# RadioInterfaceMain.net
KiCad netlist of a schematic drawn in EAGLE
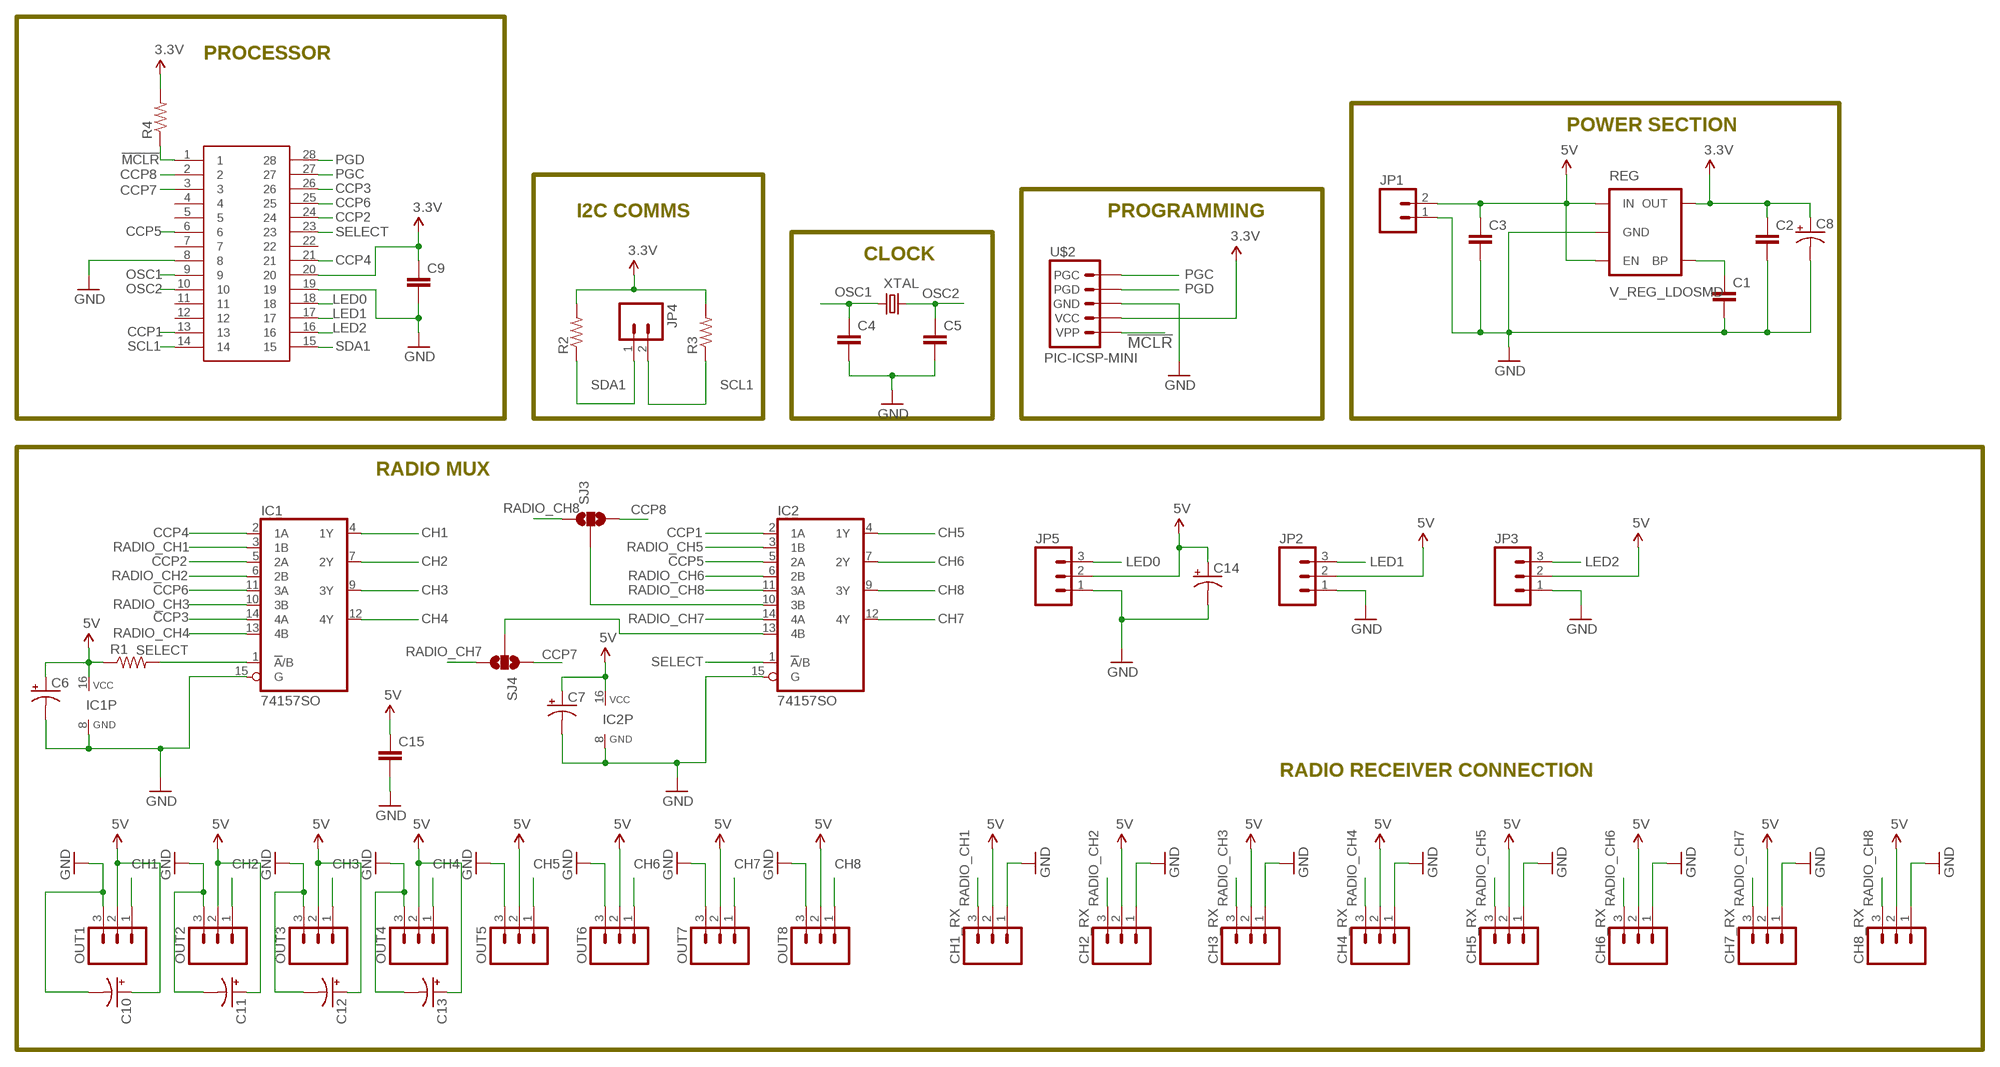
[diagram p0: schematic, sheet 1]

(export (version "E")
  (design (tool "Eeschema 10.0.6"))
  (components
    (comp (ref "C1")
      (value "CAP0603-CAP")
      (footprint "eagle-import:0603-CAP")
      (libsource (lib "eagle-import") (part "CAP0603-CAP"))
    )
    (comp (ref "C2")
      (value "CAP1210")
      (footprint "eagle-import:1210")
      (libsource (lib "eagle-import") (part "CAP1210"))
    )
    (comp (ref "C3")
      (value "CAP1210")
      (footprint "eagle-import:1210")
      (libsource (lib "eagle-import") (part "CAP1210"))
    )
    (comp (ref "C4")
      (value "CAP0603-CAP")
      (footprint "eagle-import:0603-CAP")
      (libsource (lib "eagle-import") (part "CAP0603-CAP"))
    )
    (comp (ref "C5")
      (value "CAP0603-CAP")
      (footprint "eagle-import:0603-CAP")
      (libsource (lib "eagle-import") (part "CAP0603-CAP"))
    )
    (comp (ref "C6")
      (value "CAP_POL1206")
      (footprint "eagle-import:EIA3216")
      (libsource (lib "eagle-import") (part "CAP_POL1206"))
    )
    (comp (ref "C7")
      (value "CAP_POL1206")
      (footprint "eagle-import:EIA3216")
      (libsource (lib "eagle-import") (part "CAP_POL1206"))
    )
    (comp (ref "C8")
      (value "CAP_POL1206")
      (footprint "eagle-import:EIA3216")
      (libsource (lib "eagle-import") (part "CAP_POL1206"))
    )
    (comp (ref "C9")
      (value "CAP0603-CAP")
      (footprint "eagle-import:0603-CAP")
      (libsource (lib "eagle-import") (part "CAP0603-CAP"))
    )
    (comp (ref "C10")
      (value "CAP_POL1206")
      (footprint "eagle-import:EIA3216")
      (libsource (lib "eagle-import") (part "CAP_POL1206"))
    )
    (comp (ref "C11")
      (value "CAP_POL1206")
      (footprint "eagle-import:EIA3216")
      (libsource (lib "eagle-import") (part "CAP_POL1206"))
    )
    (comp (ref "C12")
      (value "CAP_POL1206")
      (footprint "eagle-import:EIA3216")
      (libsource (lib "eagle-import") (part "CAP_POL1206"))
    )
    (comp (ref "C13")
      (value "CAP_POL1206")
      (footprint "eagle-import:EIA3216")
      (libsource (lib "eagle-import") (part "CAP_POL1206"))
    )
    (comp (ref "C14")
      (value "CAP_POL1206")
      (footprint "eagle-import:EIA3216")
      (libsource (lib "eagle-import") (part "CAP_POL1206"))
    )
    (comp (ref "C15")
      (value "CAP0603-CAP")
      (footprint "eagle-import:0603-CAP")
      (libsource (lib "eagle-import") (part "CAP0603-CAP"))
    )
    (comp (ref "CH1_RX")
      (value "M03PTH")
      (footprint "eagle-import:1X03")
      (libsource (lib "eagle-import") (part "M03PTH"))
    )
    (comp (ref "CH2_RX")
      (value "M03PTH")
      (footprint "eagle-import:1X03")
      (libsource (lib "eagle-import") (part "M03PTH"))
    )
    (comp (ref "CH3_RX")
      (value "M03PTH")
      (footprint "eagle-import:1X03")
      (libsource (lib "eagle-import") (part "M03PTH"))
    )
    (comp (ref "CH4_RX")
      (value "M03PTH")
      (footprint "eagle-import:1X03")
      (libsource (lib "eagle-import") (part "M03PTH"))
    )
    (comp (ref "CH5_RX")
      (value "M03PTH")
      (footprint "eagle-import:1X03")
      (libsource (lib "eagle-import") (part "M03PTH"))
    )
    (comp (ref "CH6_RX")
      (value "M03PTH")
      (footprint "eagle-import:1X03")
      (libsource (lib "eagle-import") (part "M03PTH"))
    )
    (comp (ref "CH7_RX")
      (value "M03PTH")
      (footprint "eagle-import:1X03")
      (libsource (lib "eagle-import") (part "M03PTH"))
    )
    (comp (ref "CH8_RX")
      (value "M03PTH")
      (footprint "eagle-import:1X03")
      (libsource (lib "eagle-import") (part "M03PTH"))
    )
    (comp (ref "IC1")
      (value "74157SO")
      (footprint "eagle-import:SO016")
      (libsource (lib "eagle-import") (part "74157SO"))
    )
    (comp (ref "IC2")
      (value "74157SO")
      (footprint "eagle-import:SO016")
      (libsource (lib "eagle-import") (part "74157SO"))
    )
    (comp (ref "JP1")
      (value "M02-JST-2MM-SMT")
      (footprint "eagle-import:JST-2-SMD")
      (libsource (lib "eagle-import") (part "M02-JST-2MM-SMT"))
    )
    (comp (ref "JP2")
      (value "M03JST-PTH")
      (footprint "eagle-import:JST-3-PTH")
      (libsource (lib "eagle-import") (part "M03JST-PTH"))
    )
    (comp (ref "JP3")
      (value "M03JST-PTH")
      (footprint "eagle-import:JST-3-PTH")
      (libsource (lib "eagle-import") (part "M03JST-PTH"))
    )
    (comp (ref "JP4")
      (value "M02-JST-2MM-SMT")
      (footprint "eagle-import:JST-2-SMD")
      (libsource (lib "eagle-import") (part "M02-JST-2MM-SMT"))
    )
    (comp (ref "JP5")
      (value "M03JST-PTH")
      (footprint "eagle-import:JST-3-PTH")
      (libsource (lib "eagle-import") (part "M03JST-PTH"))
    )
    (comp (ref "OUT1")
      (value "M03PTH")
      (footprint "eagle-import:1X03")
      (libsource (lib "eagle-import") (part "M03PTH"))
    )
    (comp (ref "OUT2")
      (value "M03PTH")
      (footprint "eagle-import:1X03")
      (libsource (lib "eagle-import") (part "M03PTH"))
    )
    (comp (ref "OUT3")
      (value "M03PTH")
      (footprint "eagle-import:1X03")
      (libsource (lib "eagle-import") (part "M03PTH"))
    )
    (comp (ref "OUT4")
      (value "M03PTH")
      (footprint "eagle-import:1X03")
      (libsource (lib "eagle-import") (part "M03PTH"))
    )
    (comp (ref "OUT5")
      (value "M03PTH")
      (footprint "eagle-import:1X03")
      (libsource (lib "eagle-import") (part "M03PTH"))
    )
    (comp (ref "OUT6")
      (value "M03PTH")
      (footprint "eagle-import:1X03")
      (libsource (lib "eagle-import") (part "M03PTH"))
    )
    (comp (ref "OUT7")
      (value "M03PTH")
      (footprint "eagle-import:1X03")
      (libsource (lib "eagle-import") (part "M03PTH"))
    )
    (comp (ref "OUT8")
      (value "M03PTH")
      (footprint "eagle-import:1X03")
      (libsource (lib "eagle-import") (part "M03PTH"))
    )
    (comp (ref "PIC18F26K22")
      (value "SSOP28")
      (footprint "eagle-import:SSOP28DB")
      (libsource (lib "eagle-import") (part "SSOP28"))
    )
    (comp (ref "R1")
      (value "RESISTOR0603-RES")
      (footprint "eagle-import:0603-RES")
      (libsource (lib "eagle-import") (part "RESISTOR0603-RES"))
    )
    (comp (ref "R2")
      (value "RESISTOR0603-RES")
      (footprint "eagle-import:0603-RES")
      (libsource (lib "eagle-import") (part "RESISTOR0603-RES"))
    )
    (comp (ref "R3")
      (value "RESISTOR0603-RES")
      (footprint "eagle-import:0603-RES")
      (libsource (lib "eagle-import") (part "RESISTOR0603-RES"))
    )
    (comp (ref "R4")
      (value "RESISTOR0603-RES")
      (footprint "eagle-import:0603-RES")
      (libsource (lib "eagle-import") (part "RESISTOR0603-RES"))
    )
    (comp (ref "REG")
      (value "V_REG_LDOSMD")
      (footprint "eagle-import:SOT23-5")
      (libsource (lib "eagle-import") (part "V_REG_LDOSMD"))
    )
    (comp (ref "SJ3")
      (value "SOLDERJUMPER_2WAY-OLDS")
      (footprint "eagle-import:SJ_3")
      (libsource (lib "eagle-import") (part "SOLDERJUMPER_2WAY-OLDS"))
    )
    (comp (ref "SJ4")
      (value "SOLDERJUMPER_2WAY-OLDS")
      (footprint "eagle-import:SJ_3")
      (libsource (lib "eagle-import") (part "SOLDERJUMPER_2WAY-OLDS"))
    )
    (comp (ref "U$2")
      (value "PIC-ICSP-MINI")
      (footprint "eagle-import:PIC-ICSP-MINI")
      (libsource (lib "eagle-import") (part "PIC-ICSP-MINI"))
    )
    (comp (ref "XTAL")
      (value "CRYSTAL5X3")
      (footprint "eagle-import:CRYSTAL-SMD-5X3")
      (libsource (lib "eagle-import") (part "CRYSTAL5X3"))
    )
  )
  (nets
    (net (code "1") (name "/CCP1") (class "Default")
      (node (ref "IC2") (pin "2") (pinfunction "1A_2") (pintype "input"))
      (node (ref "PIC18F26K22") (pin "13") (pinfunction "13_13") (pintype "bidirectional"))
    )
    (net (code "2") (name "/CCP2") (class "Default")
      (node (ref "IC1") (pin "5") (pinfunction "2A_5") (pintype "input"))
      (node (ref "PIC18F26K22") (pin "24") (pinfunction "24_24") (pintype "bidirectional"))
    )
    (net (code "3") (name "/CCP3") (class "Default")
      (node (ref "IC1") (pin "14") (pinfunction "4A_14") (pintype "input"))
      (node (ref "PIC18F26K22") (pin "26") (pinfunction "26_26") (pintype "bidirectional"))
    )
    (net (code "4") (name "/CCP4") (class "Default")
      (node (ref "IC1") (pin "2") (pinfunction "1A_2") (pintype "input"))
      (node (ref "PIC18F26K22") (pin "21") (pinfunction "21_21") (pintype "bidirectional"))
    )
    (net (code "5") (name "/CCP5") (class "Default")
      (node (ref "IC2") (pin "5") (pinfunction "2A_5") (pintype "input"))
      (node (ref "PIC18F26K22") (pin "6") (pinfunction "6_6") (pintype "bidirectional"))
    )
    (net (code "6") (name "/CCP6") (class "Default")
      (node (ref "IC1") (pin "11") (pinfunction "3A_11") (pintype "input"))
      (node (ref "PIC18F26K22") (pin "25") (pinfunction "25_25") (pintype "bidirectional"))
    )
    (net (code "7") (name "/CCP7") (class "Default")
      (node (ref "PIC18F26K22") (pin "3") (pinfunction "3_3") (pintype "bidirectional"))
      (node (ref "SJ4") (pin "1") (pinfunction "1_1") (pintype "passive"))
    )
    (net (code "8") (name "/CCP8") (class "Default")
      (node (ref "PIC18F26K22") (pin "2") (pinfunction "2_2") (pintype "bidirectional"))
      (node (ref "SJ3") (pin "3") (pinfunction "3_3") (pintype "passive"))
    )
    (net (code "9") (name "/CH1") (class "Default")
      (node (ref "IC1") (pin "4") (pinfunction "1Y_4") (pintype "output"))
      (node (ref "OUT1") (pin "1") (pinfunction "1_1") (pintype "passive"))
    )
    (net (code "10") (name "/CH2") (class "Default")
      (node (ref "IC1") (pin "7") (pinfunction "2Y_7") (pintype "output"))
      (node (ref "OUT2") (pin "1") (pinfunction "1_1") (pintype "passive"))
    )
    (net (code "11") (name "/CH3") (class "Default")
      (node (ref "IC1") (pin "9") (pinfunction "3Y_9") (pintype "output"))
      (node (ref "OUT3") (pin "1") (pinfunction "1_1") (pintype "passive"))
    )
    (net (code "12") (name "/CH4") (class "Default")
      (node (ref "IC1") (pin "12") (pinfunction "4Y_12") (pintype "output"))
      (node (ref "OUT4") (pin "1") (pinfunction "1_1") (pintype "passive"))
    )
    (net (code "13") (name "/CH5") (class "Default")
      (node (ref "IC2") (pin "4") (pinfunction "1Y_4") (pintype "output"))
      (node (ref "OUT5") (pin "1") (pinfunction "1_1") (pintype "passive"))
    )
    (net (code "14") (name "/CH6") (class "Default")
      (node (ref "IC2") (pin "7") (pinfunction "2Y_7") (pintype "output"))
      (node (ref "OUT6") (pin "1") (pinfunction "1_1") (pintype "passive"))
    )
    (net (code "15") (name "/CH7") (class "Default")
      (node (ref "IC2") (pin "12") (pinfunction "4Y_12") (pintype "output"))
      (node (ref "OUT7") (pin "1") (pinfunction "1_1") (pintype "passive"))
    )
    (net (code "16") (name "/CH8") (class "Default")
      (node (ref "IC2") (pin "9") (pinfunction "3Y_9") (pintype "output"))
      (node (ref "OUT8") (pin "1") (pinfunction "1_1") (pintype "passive"))
    )
    (net (code "17") (name "/LED0") (class "Default")
      (node (ref "JP5") (pin "3") (pinfunction "3_3") (pintype "passive"))
      (node (ref "PIC18F26K22") (pin "18") (pinfunction "18_18") (pintype "bidirectional"))
    )
    (net (code "18") (name "/LED1") (class "Default")
      (node (ref "JP2") (pin "3") (pinfunction "3_3") (pintype "passive"))
      (node (ref "PIC18F26K22") (pin "17") (pinfunction "17_17") (pintype "bidirectional"))
    )
    (net (code "19") (name "/LED2") (class "Default")
      (node (ref "JP3") (pin "3") (pinfunction "3_3") (pintype "passive"))
      (node (ref "PIC18F26K22") (pin "16") (pinfunction "16_16") (pintype "bidirectional"))
    )
    (net (code "20") (name "/OSC1") (class "Default")
      (node (ref "C4") (pin "1") (pinfunction "1_1") (pintype "passive"))
      (node (ref "PIC18F26K22") (pin "9") (pinfunction "9_9") (pintype "bidirectional"))
      (node (ref "XTAL") (pin "1") (pinfunction "1_1") (pintype "passive"))
    )
    (net (code "21") (name "/OSC2") (class "Default")
      (node (ref "C5") (pin "1") (pinfunction "1_1") (pintype "passive"))
      (node (ref "PIC18F26K22") (pin "10") (pinfunction "10_10") (pintype "bidirectional"))
      (node (ref "XTAL") (pin "3") (pinfunction "2_3") (pintype "passive"))
    )
    (net (code "22") (name "/PGC") (class "Default")
      (node (ref "PIC18F26K22") (pin "27") (pinfunction "27_27") (pintype "bidirectional"))
      (node (ref "U$2") (pin "5") (pinfunction "PGC_5") (pintype "passive"))
    )
    (net (code "23") (name "/PGD") (class "Default")
      (node (ref "PIC18F26K22") (pin "28") (pinfunction "28_28") (pintype "bidirectional"))
      (node (ref "U$2") (pin "4") (pinfunction "PGD_4") (pintype "passive"))
    )
    (net (code "24") (name "/RADIO_CH1") (class "Default")
      (node (ref "CH1_RX") (pin "3") (pinfunction "3_3") (pintype "passive"))
      (node (ref "IC1") (pin "3") (pinfunction "1B_3") (pintype "input"))
    )
    (net (code "25") (name "/RADIO_CH2") (class "Default")
      (node (ref "CH2_RX") (pin "3") (pinfunction "3_3") (pintype "passive"))
      (node (ref "IC1") (pin "6") (pinfunction "2B_6") (pintype "input"))
    )
    (net (code "26") (name "/RADIO_CH3") (class "Default")
      (node (ref "CH3_RX") (pin "3") (pinfunction "3_3") (pintype "passive"))
      (node (ref "IC1") (pin "10") (pinfunction "3B_10") (pintype "input"))
    )
    (net (code "27") (name "/RADIO_CH4") (class "Default")
      (node (ref "CH4_RX") (pin "3") (pinfunction "3_3") (pintype "passive"))
      (node (ref "IC1") (pin "13") (pinfunction "4B_13") (pintype "input"))
    )
    (net (code "28") (name "/RADIO_CH5") (class "Default")
      (node (ref "CH5_RX") (pin "3") (pinfunction "3_3") (pintype "passive"))
      (node (ref "IC2") (pin "3") (pinfunction "1B_3") (pintype "input"))
    )
    (net (code "29") (name "/RADIO_CH6") (class "Default")
      (node (ref "CH6_RX") (pin "3") (pinfunction "3_3") (pintype "passive"))
      (node (ref "IC2") (pin "6") (pinfunction "2B_6") (pintype "input"))
    )
    (net (code "30") (name "/RADIO_CH7") (class "Default")
      (node (ref "CH7_RX") (pin "3") (pinfunction "3_3") (pintype "passive"))
      (node (ref "IC2") (pin "14") (pinfunction "4A_14") (pintype "input"))
      (node (ref "SJ4") (pin "3") (pinfunction "3_3") (pintype "passive"))
    )
    (net (code "31") (name "/RADIO_CH8") (class "Default")
      (node (ref "CH8_RX") (pin "3") (pinfunction "3_3") (pintype "passive"))
      (node (ref "IC2") (pin "11") (pinfunction "3A_11") (pintype "input"))
      (node (ref "SJ3") (pin "1") (pinfunction "1_1") (pintype "passive"))
    )
    (net (code "32") (name "/SCL1") (class "Default")
      (node (ref "JP4") (pin "2") (pinfunction "2_2") (pintype "passive"))
      (node (ref "PIC18F26K22") (pin "14") (pinfunction "14_14") (pintype "bidirectional"))
      (node (ref "R3") (pin "1") (pinfunction "1_1") (pintype "passive"))
    )
    (net (code "33") (name "/SDA1") (class "Default")
      (node (ref "JP4") (pin "1") (pinfunction "1_1") (pintype "passive"))
      (node (ref "PIC18F26K22") (pin "15") (pinfunction "15_15") (pintype "bidirectional"))
      (node (ref "R2") (pin "1") (pinfunction "1_1") (pintype "passive"))
    )
    (net (code "34") (name "/SELECT") (class "Default")
      (node (ref "IC1") (pin "1") (pinfunction "~{A}/B_1") (pintype "input"))
      (node (ref "IC2") (pin "1") (pinfunction "~{A}/B_1") (pintype "input"))
      (node (ref "PIC18F26K22") (pin "23") (pinfunction "23_23") (pintype "bidirectional"))
      (node (ref "R1") (pin "2") (pinfunction "2_2") (pintype "passive"))
    )
    (net (code "35") (name "/~{MCLR}") (class "Default")
      (node (ref "PIC18F26K22") (pin "1") (pinfunction "1_1") (pintype "bidirectional"))
      (node (ref "R4") (pin "1") (pinfunction "1_1") (pintype "passive"))
      (node (ref "U$2") (pin "1") (pinfunction "VPP_1") (pintype "passive"))
    )
    (net (code "36") (name "3.3V") (class "Default")
      (node (ref "C2") (pin "1") (pinfunction "1_1") (pintype "passive"))
      (node (ref "C8") (pin "A") (pinfunction "+_A") (pintype "passive"))
      (node (ref "C9") (pin "1") (pinfunction "1_1") (pintype "passive"))
      (node (ref "PIC18F26K22") (pin "20") (pinfunction "20_20") (pintype "bidirectional"))
      (node (ref "R2") (pin "2") (pinfunction "2_2") (pintype "passive"))
      (node (ref "R3") (pin "2") (pinfunction "2_2") (pintype "passive"))
      (node (ref "R4") (pin "2") (pinfunction "2_2") (pintype "passive"))
      (node (ref "REG") (pin "5") (pinfunction "OUT_5") (pintype "passive"))
      (node (ref "U$2") (pin "2") (pinfunction "VCC_2") (pintype "passive"))
    )
    (net (code "37") (name "5V") (class "Default")
      (node (ref "C10") (pin "A") (pinfunction "+_A") (pintype "passive"))
      (node (ref "C11") (pin "A") (pinfunction "+_A") (pintype "passive"))
      (node (ref "C12") (pin "A") (pinfunction "+_A") (pintype "passive"))
      (node (ref "C13") (pin "A") (pinfunction "+_A") (pintype "passive"))
      (node (ref "C14") (pin "A") (pinfunction "+_A") (pintype "passive"))
      (node (ref "C15") (pin "1") (pinfunction "1_1") (pintype "passive"))
      (node (ref "C3") (pin "1") (pinfunction "1_1") (pintype "passive"))
      (node (ref "C6") (pin "A") (pinfunction "+_A") (pintype "passive"))
      (node (ref "C7") (pin "A") (pinfunction "+_A") (pintype "passive"))
      (node (ref "CH1_RX") (pin "2") (pinfunction "2_2") (pintype "passive"))
      (node (ref "CH2_RX") (pin "2") (pinfunction "2_2") (pintype "passive"))
      (node (ref "CH3_RX") (pin "2") (pinfunction "2_2") (pintype "passive"))
      (node (ref "CH4_RX") (pin "2") (pinfunction "2_2") (pintype "passive"))
      (node (ref "CH5_RX") (pin "2") (pinfunction "2_2") (pintype "passive"))
      (node (ref "CH6_RX") (pin "2") (pinfunction "2_2") (pintype "passive"))
      (node (ref "CH7_RX") (pin "2") (pinfunction "2_2") (pintype "passive"))
      (node (ref "CH8_RX") (pin "2") (pinfunction "2_2") (pintype "passive"))
      (node (ref "IC1") (pin "16") (pinfunction "VCC_16") (pintype "power_in"))
      (node (ref "IC2") (pin "16") (pinfunction "VCC_16") (pintype "power_in"))
      (node (ref "JP1") (pin "2") (pinfunction "2_2") (pintype "passive"))
      (node (ref "JP2") (pin "2") (pinfunction "2_2") (pintype "passive"))
      (node (ref "JP3") (pin "2") (pinfunction "2_2") (pintype "passive"))
      (node (ref "JP5") (pin "2") (pinfunction "2_2") (pintype "passive"))
      (node (ref "OUT1") (pin "2") (pinfunction "2_2") (pintype "passive"))
      (node (ref "OUT2") (pin "2") (pinfunction "2_2") (pintype "passive"))
      (node (ref "OUT3") (pin "2") (pinfunction "2_2") (pintype "passive"))
      (node (ref "OUT4") (pin "2") (pinfunction "2_2") (pintype "passive"))
      (node (ref "OUT5") (pin "2") (pinfunction "2_2") (pintype "passive"))
      (node (ref "OUT6") (pin "2") (pinfunction "2_2") (pintype "passive"))
      (node (ref "OUT7") (pin "2") (pinfunction "2_2") (pintype "passive"))
      (node (ref "OUT8") (pin "2") (pinfunction "2_2") (pintype "passive"))
      (node (ref "R1") (pin "1") (pinfunction "1_1") (pintype "passive"))
      (node (ref "REG") (pin "1") (pinfunction "IN_1") (pintype "input"))
      (node (ref "REG") (pin "3") (pinfunction "EN_3") (pintype "input"))
    )
    (net (code "38") (name "GND") (class "Default")
      (node (ref "C1") (pin "2") (pinfunction "2_2") (pintype "passive"))
      (node (ref "C10") (pin "C") (pinfunction "-_C") (pintype "passive"))
      (node (ref "C11") (pin "C") (pinfunction "-_C") (pintype "passive"))
      (node (ref "C12") (pin "C") (pinfunction "-_C") (pintype "passive"))
      (node (ref "C13") (pin "C") (pinfunction "-_C") (pintype "passive"))
      (node (ref "C14") (pin "C") (pinfunction "-_C") (pintype "passive"))
      (node (ref "C15") (pin "2") (pinfunction "2_2") (pintype "passive"))
      (node (ref "C2") (pin "2") (pinfunction "2_2") (pintype "passive"))
      (node (ref "C3") (pin "2") (pinfunction "2_2") (pintype "passive"))
      (node (ref "C4") (pin "2") (pinfunction "2_2") (pintype "passive"))
      (node (ref "C5") (pin "2") (pinfunction "2_2") (pintype "passive"))
      (node (ref "C6") (pin "C") (pinfunction "-_C") (pintype "passive"))
      (node (ref "C7") (pin "C") (pinfunction "-_C") (pintype "passive"))
      (node (ref "C8") (pin "C") (pinfunction "-_C") (pintype "passive"))
      (node (ref "C9") (pin "2") (pinfunction "2_2") (pintype "passive"))
      (node (ref "CH1_RX") (pin "1") (pinfunction "1_1") (pintype "passive"))
      (node (ref "CH2_RX") (pin "1") (pinfunction "1_1") (pintype "passive"))
      (node (ref "CH3_RX") (pin "1") (pinfunction "1_1") (pintype "passive"))
      (node (ref "CH4_RX") (pin "1") (pinfunction "1_1") (pintype "passive"))
      (node (ref "CH5_RX") (pin "1") (pinfunction "1_1") (pintype "passive"))
      (node (ref "CH6_RX") (pin "1") (pinfunction "1_1") (pintype "passive"))
      (node (ref "CH7_RX") (pin "1") (pinfunction "1_1") (pintype "passive"))
      (node (ref "CH8_RX") (pin "1") (pinfunction "1_1") (pintype "passive"))
      (node (ref "IC1") (pin "15") (pinfunction "G_15") (pintype "input"))
      (node (ref "IC1") (pin "8") (pinfunction "GND_8") (pintype "power_in"))
      (node (ref "IC2") (pin "15") (pinfunction "G_15") (pintype "input"))
      (node (ref "IC2") (pin "8") (pinfunction "GND_8") (pintype "power_in"))
      (node (ref "JP1") (pin "1") (pinfunction "1_1") (pintype "passive"))
      (node (ref "JP2") (pin "1") (pinfunction "1_1") (pintype "passive"))
      (node (ref "JP3") (pin "1") (pinfunction "1_1") (pintype "passive"))
      (node (ref "JP5") (pin "1") (pinfunction "1_1") (pintype "passive"))
      (node (ref "OUT1") (pin "3") (pinfunction "3_3") (pintype "passive"))
      (node (ref "OUT2") (pin "3") (pinfunction "3_3") (pintype "passive"))
      (node (ref "OUT3") (pin "3") (pinfunction "3_3") (pintype "passive"))
      (node (ref "OUT4") (pin "3") (pinfunction "3_3") (pintype "passive"))
      (node (ref "OUT5") (pin "3") (pinfunction "3_3") (pintype "passive"))
      (node (ref "OUT6") (pin "3") (pinfunction "3_3") (pintype "passive"))
      (node (ref "OUT7") (pin "3") (pinfunction "3_3") (pintype "passive"))
      (node (ref "OUT8") (pin "3") (pinfunction "3_3") (pintype "passive"))
      (node (ref "PIC18F26K22") (pin "19") (pinfunction "19_19") (pintype "bidirectional"))
      (node (ref "PIC18F26K22") (pin "8") (pinfunction "8_8") (pintype "bidirectional"))
      (node (ref "REG") (pin "2") (pinfunction "GND_2") (pintype "input"))
      (node (ref "U$2") (pin "3") (pinfunction "GND_3") (pintype "passive"))
    )
    (net (code "39") (name "Net-(IC2A-3B)") (class "Default")
      (node (ref "IC2") (pin "10") (pinfunction "3B_10") (pintype "input"))
      (node (ref "SJ3") (pin "2") (pinfunction "2_2") (pintype "passive"))
    )
    (net (code "40") (name "Net-(IC2A-4B)") (class "Default")
      (node (ref "IC2") (pin "13") (pinfunction "4B_13") (pintype "input"))
      (node (ref "SJ4") (pin "2") (pinfunction "2_2") (pintype "passive"))
    )
    (net (code "41") (name "Net-(REG-BP)") (class "Default")
      (node (ref "C1") (pin "1") (pinfunction "1_1") (pintype "passive"))
      (node (ref "REG") (pin "4") (pinfunction "BP_4") (pintype "input"))
    )
    (net (code "42") (name "unconnected-(PIC18F26K22-Pad4)") (class "Default")
      (node (ref "PIC18F26K22") (pin "4") (pinfunction "4_4") (pintype "bidirectional"))
    )
    (net (code "43") (name "unconnected-(PIC18F26K22-Pad5)") (class "Default")
      (node (ref "PIC18F26K22") (pin "5") (pinfunction "5_5") (pintype "bidirectional"))
    )
    (net (code "44") (name "unconnected-(PIC18F26K22-Pad7)") (class "Default")
      (node (ref "PIC18F26K22") (pin "7") (pinfunction "7_7") (pintype "bidirectional"))
    )
    (net (code "45") (name "unconnected-(PIC18F26K22-Pad11)") (class "Default")
      (node (ref "PIC18F26K22") (pin "11") (pinfunction "11_11") (pintype "bidirectional"))
    )
    (net (code "46") (name "unconnected-(PIC18F26K22-Pad12)") (class "Default")
      (node (ref "PIC18F26K22") (pin "12") (pinfunction "12_12") (pintype "bidirectional"))
    )
    (net (code "47") (name "unconnected-(PIC18F26K22-Pad22)") (class "Default")
      (node (ref "PIC18F26K22") (pin "22") (pinfunction "22_22") (pintype "bidirectional"))
    )
  )
)
